# PCB1.net
KiCad netlist of a schematic drawn in Altium Designer
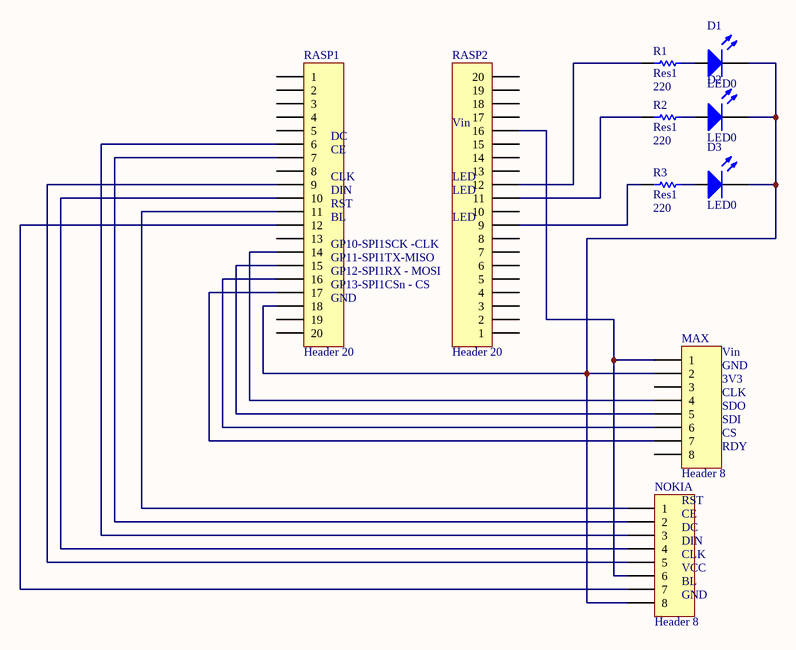
[diagram p0: PCB1.SchDoc]

(export (version "E")
  (design (tool "Eeschema 10.0.6"))
  (components
    (comp (ref "D1")
      (value "LED0")
      (footprint "LED-0")
      (description "Typical INFRARED GaAs LED")
      (fields (field (name "PUBLISHER") "Altium Limited"))
      (libsource (lib "Miscellaneous Devices") (part "LED0"))
    )
    (comp (ref "D2")
      (value "LED0")
      (footprint "LED-0")
      (description "Typical INFRARED GaAs LED")
      (fields (field (name "PUBLISHER") "Altium Limited"))
      (libsource (lib "Miscellaneous Devices") (part "LED0"))
    )
    (comp (ref "D3")
      (value "LED0")
      (footprint "LED-0")
      (description "Typical INFRARED GaAs LED")
      (fields (field (name "PUBLISHER") "Altium Limited"))
      (libsource (lib "Miscellaneous Devices") (part "LED0"))
    )
    (comp (ref "MAX")
      (value "Header 8")
      (footprint "HDR1X8")
      (description "Header, 8-Pin")
      (fields (field (name "PUBLISHER") "Altium Limited"))
      (libsource (lib "Miscellaneous Connectors") (part "Header 8"))
    )
    (comp (ref "NOKIA")
      (value "Header 8")
      (footprint "HDR1X8")
      (description "Header, 8-Pin")
      (fields (field (name "PUBLISHER") "Altium Limited"))
      (libsource (lib "Miscellaneous Connectors") (part "Header 8"))
    )
    (comp (ref "R1")
      (value "Res1")
      (footprint "AXIAL-0.3")
      (description "Resistor")
      (fields (field (name "ALTIUM_VALUE") "220") (field (name "PUBLISHER") "Altium Limited"))
      (libsource (lib "Miscellaneous Devices") (part "Res1"))
    )
    (comp (ref "R2")
      (value "Res1")
      (footprint "AXIAL-0.3")
      (description "Resistor")
      (fields (field (name "ALTIUM_VALUE") "220") (field (name "PUBLISHER") "Altium Limited"))
      (libsource (lib "Miscellaneous Devices") (part "Res1"))
    )
    (comp (ref "R3")
      (value "Res1")
      (footprint "AXIAL-0.3")
      (description "Resistor")
      (fields (field (name "ALTIUM_VALUE") "220") (field (name "PUBLISHER") "Altium Limited"))
      (libsource (lib "Miscellaneous Devices") (part "Res1"))
    )
    (comp (ref "RASP1")
      (value "Header 20")
      (footprint "HDR1X20")
      (description "Header, 20-Pin")
      (fields (field (name "PUBLISHER") "Altium Limited"))
      (libsource (lib "") (part "Header 20_1"))
    )
    (comp (ref "RASP2")
      (value "Header 20")
      (footprint "HDR1X20")
      (description "Header, 20-Pin")
      (fields (field (name "PUBLISHER") "Altium Limited"))
      (libsource (lib "Miscellaneous Connectors") (part "Header 20"))
    )
  )
  (nets
    (net (code "1") (name "Net-(D1-A)") (class "Default")
      (node (ref "D1") (pin "1") (pinfunction "A_1") (pintype "passive"))
      (node (ref "R1") (pin "2") (pinfunction "2_2") (pintype "passive"))
    )
    (net (code "2") (name "Net-(D1-K)") (class "Default")
      (node (ref "D1") (pin "2") (pinfunction "K_2") (pintype "passive"))
      (node (ref "D2") (pin "2") (pinfunction "K_2") (pintype "passive"))
      (node (ref "D3") (pin "2") (pinfunction "K_2") (pintype "passive"))
      (node (ref "MAX") (pin "2") (pinfunction "2_2") (pintype "passive"))
      (node (ref "NOKIA") (pin "8") (pinfunction "8_8") (pintype "passive"))
      (node (ref "RASP1") (pin "18") (pinfunction "18_18") (pintype "passive"))
    )
    (net (code "3") (name "Net-(D2-A)") (class "Default")
      (node (ref "D2") (pin "1") (pinfunction "A_1") (pintype "passive"))
      (node (ref "R2") (pin "2") (pinfunction "2_2") (pintype "passive"))
    )
    (net (code "4") (name "Net-(D3-A)") (class "Default")
      (node (ref "D3") (pin "1") (pinfunction "A_1") (pintype "passive"))
      (node (ref "R3") (pin "2") (pinfunction "2_2") (pintype "passive"))
    )
    (net (code "5") (name "Net-(MAX-Pad1)") (class "Default")
      (node (ref "MAX") (pin "1") (pinfunction "1_1") (pintype "passive"))
      (node (ref "NOKIA") (pin "6") (pinfunction "6_6") (pintype "passive"))
      (node (ref "RASP2") (pin "16") (pinfunction "16_16") (pintype "passive"))
    )
    (net (code "6") (name "Net-(MAX-Pad4)") (class "Default")
      (node (ref "MAX") (pin "4") (pinfunction "4_4") (pintype "passive"))
      (node (ref "RASP1") (pin "14") (pinfunction "14_14") (pintype "passive"))
    )
    (net (code "7") (name "Net-(MAX-Pad5)") (class "Default")
      (node (ref "MAX") (pin "5") (pinfunction "5_5") (pintype "passive"))
      (node (ref "RASP1") (pin "15") (pinfunction "15_15") (pintype "passive"))
    )
    (net (code "8") (name "Net-(MAX-Pad6)") (class "Default")
      (node (ref "MAX") (pin "6") (pinfunction "6_6") (pintype "passive"))
      (node (ref "RASP1") (pin "16") (pinfunction "16_16") (pintype "passive"))
    )
    (net (code "9") (name "Net-(MAX-Pad7)") (class "Default")
      (node (ref "MAX") (pin "7") (pinfunction "7_7") (pintype "passive"))
      (node (ref "RASP1") (pin "17") (pinfunction "17_17") (pintype "passive"))
    )
    (net (code "10") (name "Net-(NOKIA-Pad1)") (class "Default")
      (node (ref "NOKIA") (pin "1") (pinfunction "1_1") (pintype "passive"))
      (node (ref "RASP1") (pin "11") (pinfunction "11_11") (pintype "passive"))
    )
    (net (code "11") (name "Net-(NOKIA-Pad2)") (class "Default")
      (node (ref "NOKIA") (pin "2") (pinfunction "2_2") (pintype "passive"))
      (node (ref "RASP1") (pin "7") (pinfunction "7_7") (pintype "passive"))
    )
    (net (code "12") (name "Net-(NOKIA-Pad3)") (class "Default")
      (node (ref "NOKIA") (pin "3") (pinfunction "3_3") (pintype "passive"))
      (node (ref "RASP1") (pin "6") (pinfunction "6_6") (pintype "passive"))
    )
    (net (code "13") (name "Net-(NOKIA-Pad4)") (class "Default")
      (node (ref "NOKIA") (pin "4") (pinfunction "4_4") (pintype "passive"))
      (node (ref "RASP1") (pin "10") (pinfunction "10_10") (pintype "passive"))
    )
    (net (code "14") (name "Net-(NOKIA-Pad5)") (class "Default")
      (node (ref "NOKIA") (pin "5") (pinfunction "5_5") (pintype "passive"))
      (node (ref "RASP1") (pin "9") (pinfunction "9_9") (pintype "passive"))
    )
    (net (code "15") (name "Net-(NOKIA-Pad7)") (class "Default")
      (node (ref "NOKIA") (pin "7") (pinfunction "7_7") (pintype "passive"))
      (node (ref "RASP1") (pin "12") (pinfunction "12_12") (pintype "passive"))
    )
    (net (code "16") (name "Net-(R1-Pad1)") (class "Default")
      (node (ref "R1") (pin "1") (pinfunction "1_1") (pintype "passive"))
      (node (ref "RASP2") (pin "12") (pinfunction "12_12") (pintype "passive"))
    )
    (net (code "17") (name "Net-(R2-Pad1)") (class "Default")
      (node (ref "R2") (pin "1") (pinfunction "1_1") (pintype "passive"))
      (node (ref "RASP2") (pin "11") (pinfunction "11_11") (pintype "passive"))
    )
    (net (code "18") (name "Net-(R3-Pad1)") (class "Default")
      (node (ref "R3") (pin "1") (pinfunction "1_1") (pintype "passive"))
      (node (ref "RASP2") (pin "9") (pinfunction "9_9") (pintype "passive"))
    )
    (net (code "19") (name "unconnected-(MAX-Pad3)") (class "Default")
      (node (ref "MAX") (pin "3") (pinfunction "3_3") (pintype "passive"))
    )
    (net (code "20") (name "unconnected-(MAX-Pad8)") (class "Default")
      (node (ref "MAX") (pin "8") (pinfunction "8_8") (pintype "passive"))
    )
    (net (code "21") (name "unconnected-(RASP1-Pad1)") (class "Default")
      (node (ref "RASP1") (pin "1") (pinfunction "1_1") (pintype "passive"))
    )
    (net (code "22") (name "unconnected-(RASP1-Pad2)") (class "Default")
      (node (ref "RASP1") (pin "2") (pinfunction "2_2") (pintype "passive"))
    )
    (net (code "23") (name "unconnected-(RASP1-Pad3)") (class "Default")
      (node (ref "RASP1") (pin "3") (pinfunction "3_3") (pintype "passive"))
    )
    (net (code "24") (name "unconnected-(RASP1-Pad4)") (class "Default")
      (node (ref "RASP1") (pin "4") (pinfunction "4_4") (pintype "passive"))
    )
    (net (code "25") (name "unconnected-(RASP1-Pad5)") (class "Default")
      (node (ref "RASP1") (pin "5") (pinfunction "5_5") (pintype "passive"))
    )
    (net (code "26") (name "unconnected-(RASP1-Pad8)") (class "Default")
      (node (ref "RASP1") (pin "8") (pinfunction "8_8") (pintype "passive"))
    )
    (net (code "27") (name "unconnected-(RASP1-Pad13)") (class "Default")
      (node (ref "RASP1") (pin "13") (pinfunction "13_13") (pintype "passive"))
    )
    (net (code "28") (name "unconnected-(RASP1-Pad19)") (class "Default")
      (node (ref "RASP1") (pin "19") (pinfunction "19_19") (pintype "passive"))
    )
    (net (code "29") (name "unconnected-(RASP1-Pad20)") (class "Default")
      (node (ref "RASP1") (pin "20") (pinfunction "20_20") (pintype "passive"))
    )
    (net (code "30") (name "unconnected-(RASP2-Pad1)") (class "Default")
      (node (ref "RASP2") (pin "1") (pinfunction "1_1") (pintype "passive"))
    )
    (net (code "31") (name "unconnected-(RASP2-Pad2)") (class "Default")
      (node (ref "RASP2") (pin "2") (pinfunction "2_2") (pintype "passive"))
    )
    (net (code "32") (name "unconnected-(RASP2-Pad3)") (class "Default")
      (node (ref "RASP2") (pin "3") (pinfunction "3_3") (pintype "passive"))
    )
    (net (code "33") (name "unconnected-(RASP2-Pad4)") (class "Default")
      (node (ref "RASP2") (pin "4") (pinfunction "4_4") (pintype "passive"))
    )
    (net (code "34") (name "unconnected-(RASP2-Pad5)") (class "Default")
      (node (ref "RASP2") (pin "5") (pinfunction "5_5") (pintype "passive"))
    )
    (net (code "35") (name "unconnected-(RASP2-Pad6)") (class "Default")
      (node (ref "RASP2") (pin "6") (pinfunction "6_6") (pintype "passive"))
    )
    (net (code "36") (name "unconnected-(RASP2-Pad7)") (class "Default")
      (node (ref "RASP2") (pin "7") (pinfunction "7_7") (pintype "passive"))
    )
    (net (code "37") (name "unconnected-(RASP2-Pad8)") (class "Default")
      (node (ref "RASP2") (pin "8") (pinfunction "8_8") (pintype "passive"))
    )
    (net (code "38") (name "unconnected-(RASP2-Pad10)") (class "Default")
      (node (ref "RASP2") (pin "10") (pinfunction "10_10") (pintype "passive"))
    )
    (net (code "39") (name "unconnected-(RASP2-Pad13)") (class "Default")
      (node (ref "RASP2") (pin "13") (pinfunction "13_13") (pintype "passive"))
    )
    (net (code "40") (name "unconnected-(RASP2-Pad14)") (class "Default")
      (node (ref "RASP2") (pin "14") (pinfunction "14_14") (pintype "passive"))
    )
    (net (code "41") (name "unconnected-(RASP2-Pad15)") (class "Default")
      (node (ref "RASP2") (pin "15") (pinfunction "15_15") (pintype "passive"))
    )
    (net (code "42") (name "unconnected-(RASP2-Pad17)") (class "Default")
      (node (ref "RASP2") (pin "17") (pinfunction "17_17") (pintype "passive"))
    )
    (net (code "43") (name "unconnected-(RASP2-Pad18)") (class "Default")
      (node (ref "RASP2") (pin "18") (pinfunction "18_18") (pintype "passive"))
    )
    (net (code "44") (name "unconnected-(RASP2-Pad19)") (class "Default")
      (node (ref "RASP2") (pin "19") (pinfunction "19_19") (pintype "passive"))
    )
    (net (code "45") (name "unconnected-(RASP2-Pad20)") (class "Default")
      (node (ref "RASP2") (pin "20") (pinfunction "20_20") (pintype "passive"))
    )
  )
)
